# TH_PROBE.net
KiCad netlist of a schematic drawn in EAGLE
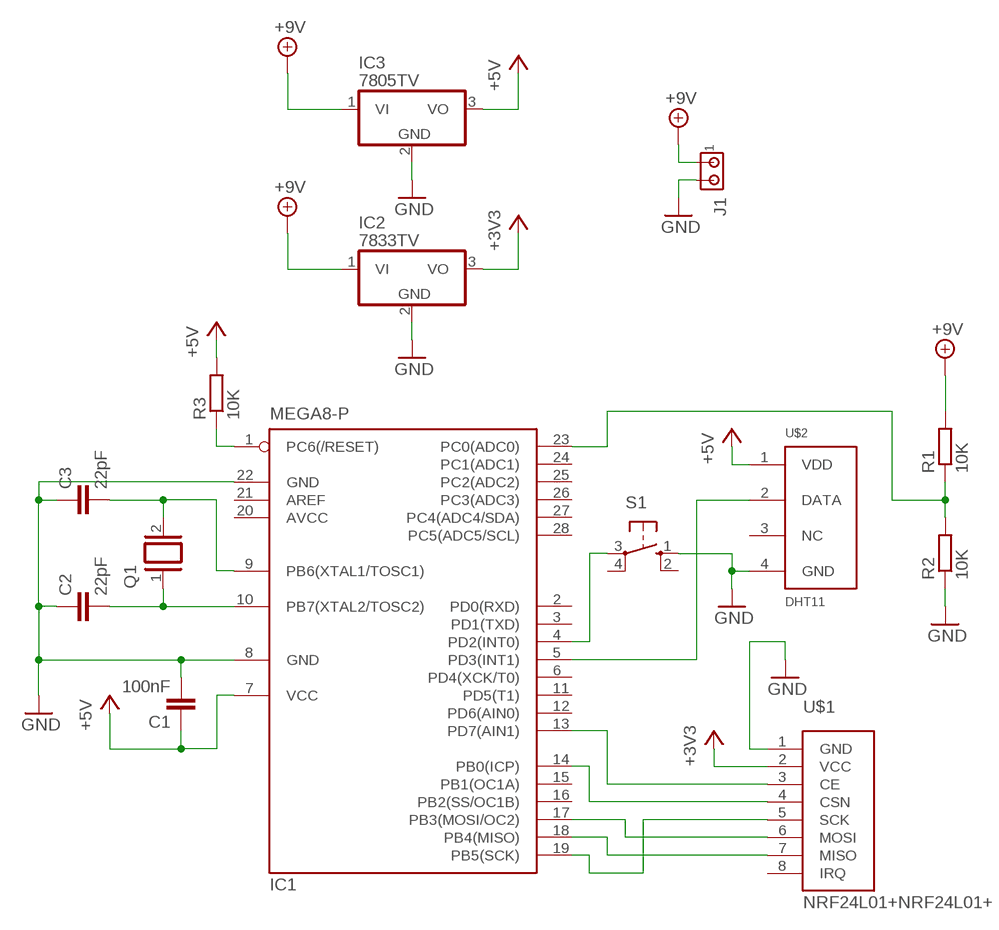
[diagram p0: schematic, sheet 1]

(export (version "E")
  (design (tool "Eeschema 10.0.6"))
  (components
    (comp (ref "C1")
      (value "100nF")
      (footprint "eagle-import:C025-025X050")
      (libsource (lib "eagle-import") (part "C-EU025-025X050"))
    )
    (comp (ref "C2")
      (value "22pF")
      (footprint "eagle-import:C025-025X050")
      (libsource (lib "eagle-import") (part "C-EU025-025X050"))
    )
    (comp (ref "C3")
      (value "22pF")
      (footprint "eagle-import:C025-025X050")
      (libsource (lib "eagle-import") (part "C-EU025-025X050"))
    )
    (comp (ref "IC1")
      (value "MEGA8-P")
      (footprint "eagle-import:DIL28-3")
      (libsource (lib "eagle-import") (part "MEGA8-P"))
    )
    (comp (ref "IC2")
      (value "7833TV")
      (footprint "eagle-import:TO220V")
      (libsource (lib "eagle-import") (part "78TV12"))
    )
    (comp (ref "IC3")
      (value "7805TV")
      (footprint "eagle-import:TO220V")
      (libsource (lib "eagle-import") (part "78TV12"))
    )
    (comp (ref "J1")
      (value "MTA02-100")
      (footprint "eagle-import:10X02MTA")
      (libsource (lib "eagle-import") (part "MTA02-100"))
    )
    (comp (ref "Q1")
      (value "XTAL/S")
      (footprint "eagle-import:QS")
      (libsource (lib "eagle-import") (part "XTAL/S"))
    )
    (comp (ref "R1")
      (value "10K")
      (footprint "eagle-import:0204_7")
      (libsource (lib "eagle-import") (part "R-EU_0204/7"))
    )
    (comp (ref "R2")
      (value "10K")
      (footprint "eagle-import:0204_7")
      (libsource (lib "eagle-import") (part "R-EU_0204/7"))
    )
    (comp (ref "R3")
      (value "10K")
      (footprint "eagle-import:0204_7")
      (libsource (lib "eagle-import") (part "R-EU_0204/7"))
    )
    (comp (ref "S1")
      (value "10-XX")
      (footprint "eagle-import:B3F-10XX")
      (fields (field (name "MPN") "B3F-1000"))
      (libsource (lib "eagle-import") (part "10-XX"))
    )
    (comp (ref "U$1")
      (value "NRF24L01+NRF24L01+")
      (footprint "eagle-import:NRF24L01+")
      (libsource (lib "eagle-import") (part "NRF24L01+NRF24L01+"))
    )
    (comp (ref "U$2")
      (value "DHT11")
      (footprint "eagle-import:DHT11")
      (libsource (lib "eagle-import") (part "DHT11"))
    )
  )
  (nets
    (net (code "1") (name "+3V3") (class "Default")
      (node (ref "IC2") (pin "3") (pinfunction "VO_3") (pintype "passive"))
      (node (ref "U$1") (pin "2") (pinfunction "VCC_2") (pintype "input"))
    )
    (net (code "2") (name "+5V") (class "Default")
      (node (ref "C1") (pin "1") (pinfunction "1_1") (pintype "passive"))
      (node (ref "IC1") (pin "7") (pinfunction "VCC_7") (pintype "power_in"))
      (node (ref "IC3") (pin "3") (pinfunction "VO_3") (pintype "passive"))
      (node (ref "R3") (pin "2") (pinfunction "2_2") (pintype "passive"))
      (node (ref "U$2") (pin "1") (pinfunction "VDD_1") (pintype "power_in"))
    )
    (net (code "3") (name "+9V") (class "Default")
      (node (ref "IC2") (pin "1") (pinfunction "VI_1") (pintype "input"))
      (node (ref "IC3") (pin "1") (pinfunction "VI_1") (pintype "input"))
      (node (ref "J1") (pin "1") (pinfunction "1_1") (pintype "passive"))
      (node (ref "R1") (pin "2") (pinfunction "2_2") (pintype "passive"))
    )
    (net (code "4") (name "/AVCC") (class "Default")
      (node (ref "IC1") (pin "20") (pinfunction "AVCC_20") (pintype "power_in"))
    )
    (net (code "5") (name "GND") (class "Default")
      (node (ref "C1") (pin "2") (pinfunction "2_2") (pintype "passive"))
      (node (ref "C2") (pin "1") (pinfunction "1_1") (pintype "passive"))
      (node (ref "C3") (pin "1") (pinfunction "1_1") (pintype "passive"))
      (node (ref "IC1") (pin "22") (pinfunction "GND_22") (pintype "power_in"))
      (node (ref "IC1") (pin "8") (pinfunction "GND_8") (pintype "power_in"))
      (node (ref "IC2") (pin "2") (pinfunction "GND_2") (pintype "passive"))
      (node (ref "IC3") (pin "2") (pinfunction "GND_2") (pintype "passive"))
      (node (ref "J1") (pin "2") (pinfunction "2_2") (pintype "passive"))
      (node (ref "R2") (pin "1") (pinfunction "1_1") (pintype "passive"))
      (node (ref "S1") (pin "1") (pinfunction "S_1") (pintype "passive"))
      (node (ref "U$1") (pin "1") (pinfunction "GND_1") (pintype "input"))
      (node (ref "U$2") (pin "4") (pinfunction "GND_4") (pintype "power_in"))
    )
    (net (code "6") (name "Net-(IC1-PB0(ICP))") (class "Default")
      (node (ref "IC1") (pin "14") (pinfunction "PB0(ICP)_14") (pintype "bidirectional"))
      (node (ref "U$1") (pin "4") (pinfunction "CSN_4") (pintype "input"))
    )
    (net (code "7") (name "Net-(IC1-PB3(MOSI{slash}OC2))") (class "Default")
      (node (ref "IC1") (pin "17") (pinfunction "PB3(MOSI/OC2)_17") (pintype "bidirectional"))
      (node (ref "U$1") (pin "6") (pinfunction "MOSI_6") (pintype "input"))
    )
    (net (code "8") (name "Net-(IC1-PB4(MISO))") (class "Default")
      (node (ref "IC1") (pin "18") (pinfunction "PB4(MISO)_18") (pintype "bidirectional"))
      (node (ref "U$1") (pin "7") (pinfunction "MISO_7") (pintype "output"))
    )
    (net (code "9") (name "Net-(IC1-PB5(SCK))") (class "Default")
      (node (ref "IC1") (pin "19") (pinfunction "PB5(SCK)_19") (pintype "bidirectional"))
      (node (ref "U$1") (pin "5") (pinfunction "SCK_5") (pintype "input"))
    )
    (net (code "10") (name "Net-(IC1-PB6(XTAL1{slash}TOSC1))") (class "Default")
      (node (ref "C3") (pin "2") (pinfunction "2_2") (pintype "passive"))
      (node (ref "IC1") (pin "9") (pinfunction "PB6(XTAL1/TOSC1)_9") (pintype "bidirectional"))
      (node (ref "Q1") (pin "2") (pinfunction "2_2") (pintype "passive"))
    )
    (net (code "11") (name "Net-(IC1-PB7(XTAL2{slash}TOSC2))") (class "Default")
      (node (ref "C2") (pin "2") (pinfunction "2_2") (pintype "passive"))
      (node (ref "IC1") (pin "10") (pinfunction "PB7(XTAL2/TOSC2)_10") (pintype "bidirectional"))
      (node (ref "Q1") (pin "1") (pinfunction "1_1") (pintype "passive"))
    )
    (net (code "12") (name "Net-(IC1-PC0(ADC0))") (class "Default")
      (node (ref "IC1") (pin "23") (pinfunction "PC0(ADC0)_23") (pintype "bidirectional"))
      (node (ref "R1") (pin "1") (pinfunction "1_1") (pintype "passive"))
      (node (ref "R2") (pin "2") (pinfunction "2_2") (pintype "passive"))
    )
    (net (code "13") (name "Net-(IC1-PC6({slash}RESET))") (class "Default")
      (node (ref "IC1") (pin "1") (pinfunction "PC6(/RESET)_1") (pintype "bidirectional"))
      (node (ref "R3") (pin "1") (pinfunction "1_1") (pintype "passive"))
    )
    (net (code "14") (name "Net-(IC1-PD2(INT0))") (class "Default")
      (node (ref "IC1") (pin "4") (pinfunction "PD2(INT0)_4") (pintype "bidirectional"))
      (node (ref "S1") (pin "3") (pinfunction "P_3") (pintype "passive"))
    )
    (net (code "15") (name "Net-(IC1-PD3(INT1))") (class "Default")
      (node (ref "IC1") (pin "5") (pinfunction "PD3(INT1)_5") (pintype "bidirectional"))
      (node (ref "U$2") (pin "2") (pinfunction "DATA_2") (pintype "bidirectional"))
    )
    (net (code "16") (name "Net-(IC1-PD7(AIN1))") (class "Default")
      (node (ref "IC1") (pin "13") (pinfunction "PD7(AIN1)_13") (pintype "bidirectional"))
      (node (ref "U$1") (pin "3") (pinfunction "CE_3") (pintype "input"))
    )
    (net (code "17") (name "unconnected-(IC1-AREF-Pad21)") (class "Default")
      (node (ref "IC1") (pin "21") (pinfunction "AREF_21") (pintype "passive"))
    )
    (net (code "18") (name "unconnected-(IC1-PB1(OC1A)-Pad15)") (class "Default")
      (node (ref "IC1") (pin "15") (pinfunction "PB1(OC1A)_15") (pintype "bidirectional"))
    )
    (net (code "19") (name "unconnected-(IC1-PB2(SS{slash}OC1B)-Pad16)") (class "Default")
      (node (ref "IC1") (pin "16") (pinfunction "PB2(SS/OC1B)_16") (pintype "bidirectional"))
    )
    (net (code "20") (name "unconnected-(IC1-PC1(ADC1)-Pad24)") (class "Default")
      (node (ref "IC1") (pin "24") (pinfunction "PC1(ADC1)_24") (pintype "bidirectional"))
    )
    (net (code "21") (name "unconnected-(IC1-PC2(ADC2)-Pad25)") (class "Default")
      (node (ref "IC1") (pin "25") (pinfunction "PC2(ADC2)_25") (pintype "bidirectional"))
    )
    (net (code "22") (name "unconnected-(IC1-PC3(ADC3)-Pad26)") (class "Default")
      (node (ref "IC1") (pin "26") (pinfunction "PC3(ADC3)_26") (pintype "bidirectional"))
    )
    (net (code "23") (name "unconnected-(IC1-PC4(ADC4{slash}SDA)-Pad27)") (class "Default")
      (node (ref "IC1") (pin "27") (pinfunction "PC4(ADC4/SDA)_27") (pintype "bidirectional"))
    )
    (net (code "24") (name "unconnected-(IC1-PC5(ADC5{slash}SCL)-Pad28)") (class "Default")
      (node (ref "IC1") (pin "28") (pinfunction "PC5(ADC5/SCL)_28") (pintype "bidirectional"))
    )
    (net (code "25") (name "unconnected-(IC1-PD0(RXD)-Pad2)") (class "Default")
      (node (ref "IC1") (pin "2") (pinfunction "PD0(RXD)_2") (pintype "bidirectional"))
    )
    (net (code "26") (name "unconnected-(IC1-PD1(TXD)-Pad3)") (class "Default")
      (node (ref "IC1") (pin "3") (pinfunction "PD1(TXD)_3") (pintype "bidirectional"))
    )
    (net (code "27") (name "unconnected-(IC1-PD4(XCK{slash}T0)-Pad6)") (class "Default")
      (node (ref "IC1") (pin "6") (pinfunction "PD4(XCK/T0)_6") (pintype "bidirectional"))
    )
    (net (code "28") (name "unconnected-(IC1-PD5(T1)-Pad11)") (class "Default")
      (node (ref "IC1") (pin "11") (pinfunction "PD5(T1)_11") (pintype "bidirectional"))
    )
    (net (code "29") (name "unconnected-(IC1-PD6(AIN0)-Pad12)") (class "Default")
      (node (ref "IC1") (pin "12") (pinfunction "PD6(AIN0)_12") (pintype "bidirectional"))
    )
    (net (code "30") (name "unconnected-(S1-P1-Pad4)") (class "Default")
      (node (ref "S1") (pin "4") (pinfunction "P1_4") (pintype "passive"))
    )
    (net (code "31") (name "unconnected-(S1-S1-Pad2)") (class "Default")
      (node (ref "S1") (pin "2") (pinfunction "S1_2") (pintype "passive"))
    )
    (net (code "32") (name "unconnected-(U$1-IRQ-Pad8)") (class "Default")
      (node (ref "U$1") (pin "8") (pinfunction "IRQ_8") (pintype "output"))
    )
    (net (code "33") (name "unconnected-(U$2-NC-Pad3)") (class "Default")
      (node (ref "U$2") (pin "3") (pinfunction "NC_3") (pintype "bidirectional"))
    )
  )
)
